# 04_Power.net
KiCad netlist of a schematic drawn in Altium Designer
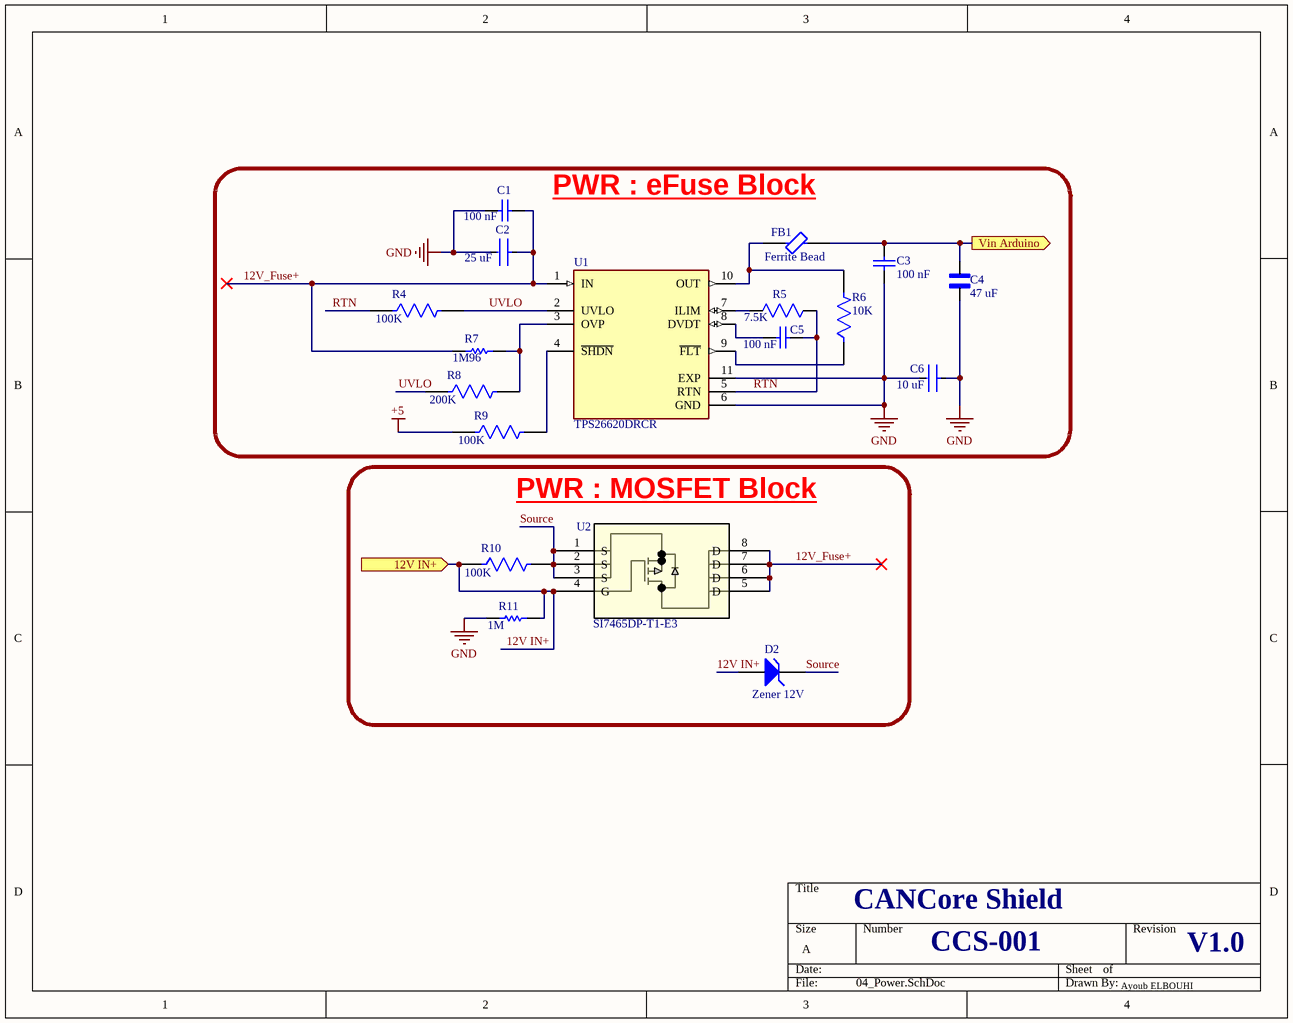
[diagram p0: 04_Power.SchDoc]

(export (version "E")
  (design (tool "Eeschema 10.0.6"))
  (components
    (comp (ref "C1")
      (value "100 nF")
      (footprint "CAPC1608X90X35ML10T15")
      (description "Chip Capacitor, 0.1 uF, +/- 10%, 50 V, -55 to 125 degC, 0603 (1608 Metric), RoHS, Tape and Reel")
      (fields (field (name "TOLERANCE") "10%") (field (name "VOLTAGE") "50V"))
      (libsource (lib "Altium Content Vault") (part "CAP-NP-2"))
    )
    (comp (ref "C2")
      (value "25 uF")
      (footprint "FP-GRM32-MFG")
      (description "CAP CER 10UF 50V X7R 1210")
      (fields (field (name "TOLERANCE") "10%") (field (name "MANUFACTURER PART NUMBER") "GRM32ER71H106KA12L"))
      (libsource (lib "Altium Content Vault") (part "11868f565c42a9108669ba33697ecf6"))
    )
    (comp (ref "C3")
      (value "100 nF")
      (footprint "CAPC1608X90X35ML10T15")
      (description "Chip Capacitor, 0.1 uF, +/- 10%, 50 V, -55 to 125 degC, 0603 (1608 Metric), RoHS, Tape and Reel")
      (fields (field (name "TOLERANCE") "10%") (field (name "VOLTAGE") "50V"))
      (libsource (lib "Altium Content Vault") (part "CAP-NP-2"))
    )
    (comp (ref "C4")
      (value "47 uF")
      (footprint "CAPC3225X270N")
      (description "SMD capacitor X7R(EIA) with capacitance 47uF Tol.10%. Rated voltage 10Vdc 125C")
      (fields (field (name "MF") "Murata Electronics") (field (name "MP") "GRM32ER71A476KE15L"))
      (libsource (lib "GRM32ER71A476KE15L") (part "GRM32ER71A476KE15L"))
    )
    (comp (ref "C5")
      (value "100 nF")
      (footprint "CAPC1608X90X35ML10T15")
      (description "Chip Capacitor, 0.1 uF, +/- 10%, 50 V, -55 to 125 degC, 0603 (1608 Metric), RoHS, Tape and Reel")
      (fields (field (name "TOLERANCE") "10%") (field (name "VOLTAGE") "50V"))
      (libsource (lib "Altium Content Vault") (part "CAP-NP-2"))
    )
    (comp (ref "C6")
      (value "10 uF")
      (footprint "FP-GCM188-0_1-IPC_C")
      (description "Ceramic Capacitor for Automotive 91pF  ±1% 100VDC X8G 0603 Paper T/R")
      (libsource (lib "Altium Content Vault") (part "02cd4be3c70576c341d710602a673aa"))
    )
    (comp (ref "D2")
      (value "Zener 12V")
      (footprint "DIOD-SOD123-2_V")
      (fields (field (name "PARTNUMBER") "BZT52C12-7-F") (field (name "MANUFACTURER") "Diodes Inc"))
      (libsource (lib "Altium Content Vault") (part "DIOD-DZEN-A1K2-2"))
    )
    (comp (ref "FB1")
      (value "Ferrite Bead")
      (footprint "FP-BLM21-0_2-t0_85-e0_5-IPC_C")
      (description "Chip Ferrite Bead, 0805, 600Ω @ 100MHz, 0.35Ω, 25%, 300mA")
      (fields (field (name "TOLERANCE") "25%"))
      (libsource (lib "Altium Content Vault") (part "5f30dd21d616792df468990f7003faa"))
    )
    (comp (ref "R4")
      (value "100K")
      (footprint "FP-RC0603-0_55-MFG")
      (description "RES SMD 100K OHM 1% 1/10W 0603")
      (fields (field (name "TOLERANCE") "1%"))
      (libsource (lib "Altium Content Vault") (part "1029c3af85768c4190bb7ad29bc67b5"))
    )
    (comp (ref "R5")
      (value "7.5K")
      (footprint "RESC1608X60N")
      (description "7.5 kOhms Â±1% 0.1W, 1/10W Chip Resistor 0603 (1608 Metric) Moisture Resistant Thick Film")
      (fields (field (name "MF") "Yageo") (field (name "MP") "RC0603FR-077K5L"))
      (libsource (lib "RC0603FR-077K5L") (part "RC0603FR-077K5L"))
    )
    (comp (ref "R6")
      (value "10K")
      (footprint "FP-RC0603-0_55-MFG")
      (description "RES 10K OHM 1% 1/10W 0603")
      (fields (field (name "TOLERANCE") "1%"))
      (libsource (lib "Altium Content Vault") (part "1029c3af85768c4190bb7ad29bc67b5"))
    )
    (comp (ref "R7")
      (value "1M96")
      (footprint "RESC0603(1608)_L")
      (description "1M96 0.1W 1% 0603 (1608 Metric)  SMD")
      (fields (field (name "POWER") "0.1 W") (field (name "TOLERANCE") "1 %"))
      (libsource (lib "Altium Content Vault") (part "RES"))
    )
    (comp (ref "R8")
      (value "200K")
      (footprint "FP-RC0603-0_55-IPC_B")
      (description "RES SMD 200K OHM 1% 1/10W 0603")
      (fields (field (name "TOLERANCE") "1%"))
      (libsource (lib "Altium Content Vault") (part "1029c3af85768c4190bb7ad29bc67b5"))
    )
    (comp (ref "R9")
      (value "100K")
      (footprint "FP-RC0603-0_55-MFG")
      (description "RES SMD 100K OHM 1% 1/10W 0603")
      (fields (field (name "TOLERANCE") "1%"))
      (libsource (lib "Altium Content Vault") (part "1029c3af85768c4190bb7ad29bc67b5"))
    )
    (comp (ref "R10")
      (value "100K")
      (footprint "FP-RC0603-0_55-MFG")
      (description "RES SMD 100K OHM 1% 1/10W 0603")
      (fields (field (name "TOLERANCE") "1%"))
      (libsource (lib "Altium Content Vault") (part "1029c3af85768c4190bb7ad29bc67b5"))
    )
    (comp (ref "R11")
      (value "1M")
      (footprint "RESC1608X55X25ML10T15")
      (description "Chip Resistor, 1 MOhm, +/- 1%, 100 mW, -55 to 155 degC, 0603 (1608 Metric), RoHS, Tape and Reel")
      (fields (field (name "TOLERANCE") "20%"))
      (libsource (lib "Altium Content Vault") (part "RES-2"))
    )
    (comp (ref "U1")
      (value "TPS26620DRCR")
      (footprint "IC_TPS26620DRCR")
      (fields (field (name "MF") "{'manufacturer': u'Texas Instruments'}"))
      (libsource (lib "TPS26620DRCR") (part "TPS26620DRCR"))
    )
    (comp (ref "U2")
      (value "SI7465DP-T1-E3")
      (footprint "PowerPAK_SO-8_VIS")
      (description "P-CHANNEL 60-V (D-S) MOSFET")
      (fields (field (name "COPYRIGHT") "Copyright (C) 2026 Ultra Librarian. All rights reserved."))
      (libsource (lib "SI7465DP-T1-E3") (part "SI7465DP-T1-E3"))
    )
  )
  (nets
    (net (code "1") (name "+5") (class "Default")
      (node (ref "R9") (pin "1") (pinfunction "1_1") (pintype "passive"))
    )
    (net (code "2") (name "/12V IN+") (class "Default")
      (node (ref "D2") (pin "1") (pinfunction "A_1") (pintype "passive"))
      (node (ref "R10") (pin "1") (pinfunction "1_1") (pintype "passive"))
      (node (ref "R11") (pin "2") (pinfunction "2_2") (pintype "passive"))
      (node (ref "U2") (pin "4") (pinfunction "G_4") (pintype "passive"))
    )
    (net (code "3") (name "/12V_Fuse+") (class "Default")
      (node (ref "C1") (pin "2") (pinfunction "2_2") (pintype "passive"))
      (node (ref "C2") (pin "1") (pinfunction "1_1") (pintype "passive"))
      (node (ref "R7") (pin "2") (pinfunction "2_2") (pintype "passive"))
      (node (ref "U1") (pin "1") (pinfunction "IN_1") (pintype "input"))
      (node (ref "U2") (pin "5") (pinfunction "D_5") (pintype "passive"))
      (node (ref "U2") (pin "6") (pinfunction "D_6") (pintype "passive"))
      (node (ref "U2") (pin "7") (pinfunction "D_7") (pintype "passive"))
      (node (ref "U2") (pin "8") (pinfunction "D_8") (pintype "passive"))
    )
    (net (code "5") (name "/RTN") (class "Default")
      (node (ref "C5") (pin "2") (pinfunction "2_2") (pintype "passive"))
      (node (ref "R4") (pin "1") (pinfunction "1_1") (pintype "passive"))
      (node (ref "R5") (pin "1") (pinfunction "R1_1") (pintype "passive"))
      (node (ref "U1") (pin "5") (pinfunction "RTN_5") (pintype "power_in"))
    )
    (net (code "6") (name "/Source") (class "Default")
      (node (ref "D2") (pin "2") (pinfunction "K_2") (pintype "passive"))
      (node (ref "R10") (pin "2") (pinfunction "2_2") (pintype "passive"))
      (node (ref "U2") (pin "1") (pinfunction "S_1") (pintype "passive"))
      (node (ref "U2") (pin "2") (pinfunction "S_2") (pintype "passive"))
      (node (ref "U2") (pin "3") (pinfunction "S_3") (pintype "passive"))
    )
    (net (code "7") (name "/UVLO") (class "Default")
      (node (ref "R4") (pin "2") (pinfunction "2_2") (pintype "passive"))
      (node (ref "R8") (pin "1") (pinfunction "1_1") (pintype "passive"))
      (node (ref "U1") (pin "2") (pinfunction "UVLO_2") (pintype "passive"))
    )
    (net (code "8") (name "/Vin Arduino") (class "Default")
      (node (ref "C3") (pin "1") (pinfunction "1_1") (pintype "passive"))
      (node (ref "C4") (pin "2") (pinfunction "2_2") (pintype "passive"))
      (node (ref "FB1") (pin "2") (pinfunction "2_2") (pintype "passive"))
    )
    (net (code "9") (name "GND") (class "Default")
      (node (ref "C1") (pin "1") (pinfunction "1_1") (pintype "passive"))
      (node (ref "C2") (pin "2") (pinfunction "2_2") (pintype "passive"))
      (node (ref "C3") (pin "2") (pinfunction "2_2") (pintype "passive"))
      (node (ref "C4") (pin "1") (pinfunction "1_1") (pintype "passive"))
      (node (ref "C6") (pin "1") (pinfunction "1_1") (pintype "passive"))
      (node (ref "C6") (pin "2") (pinfunction "2_2") (pintype "passive"))
      (node (ref "R11") (pin "1") (pinfunction "1_1") (pintype "passive"))
      (node (ref "U1") (pin "11") (pinfunction "EXP_11") (pintype "power_in"))
      (node (ref "U1") (pin "6") (pinfunction "GND_6") (pintype "power_in"))
    )
    (net (code "10") (name "Net-(R5-R2)") (class "Default")
      (node (ref "R5") (pin "2") (pinfunction "R2_2") (pintype "passive"))
      (node (ref "U1") (pin "7") (pinfunction "ILIM_7") (pintype "bidirectional"))
    )
    (net (code "11") (name "Net-(U1-DVDT)") (class "Default")
      (node (ref "C5") (pin "1") (pinfunction "1_1") (pintype "passive"))
      (node (ref "U1") (pin "8") (pinfunction "DVDT_8") (pintype "bidirectional"))
    )
    (net (code "12") (name "Net-(U1-OUT)") (class "Default")
      (node (ref "FB1") (pin "1") (pinfunction "1_1") (pintype "passive"))
      (node (ref "R6") (pin "2") (pinfunction "2_2") (pintype "passive"))
      (node (ref "U1") (pin "10") (pinfunction "OUT_10") (pintype "output"))
    )
    (net (code "13") (name "Net-(U1-OVP)") (class "Default")
      (node (ref "R7") (pin "1") (pinfunction "1_1") (pintype "passive"))
      (node (ref "R8") (pin "2") (pinfunction "2_2") (pintype "passive"))
      (node (ref "U1") (pin "3") (pinfunction "OVP_3") (pintype "passive"))
    )
    (net (code "14") (name "Net-(U1-~{FLT})") (class "Default")
      (node (ref "R6") (pin "1") (pinfunction "1_1") (pintype "passive"))
      (node (ref "U1") (pin "9") (pinfunction "~{FLT}_9") (pintype "output"))
    )
    (net (code "15") (name "Net-(U1-~{SHDN})") (class "Default")
      (node (ref "R9") (pin "2") (pinfunction "2_2") (pintype "passive"))
      (node (ref "U1") (pin "4") (pinfunction "~{SHDN}_4") (pintype "passive"))
    )
  )
)
